# ADC.net
KiCad netlist of a schematic drawn in Altium Designer
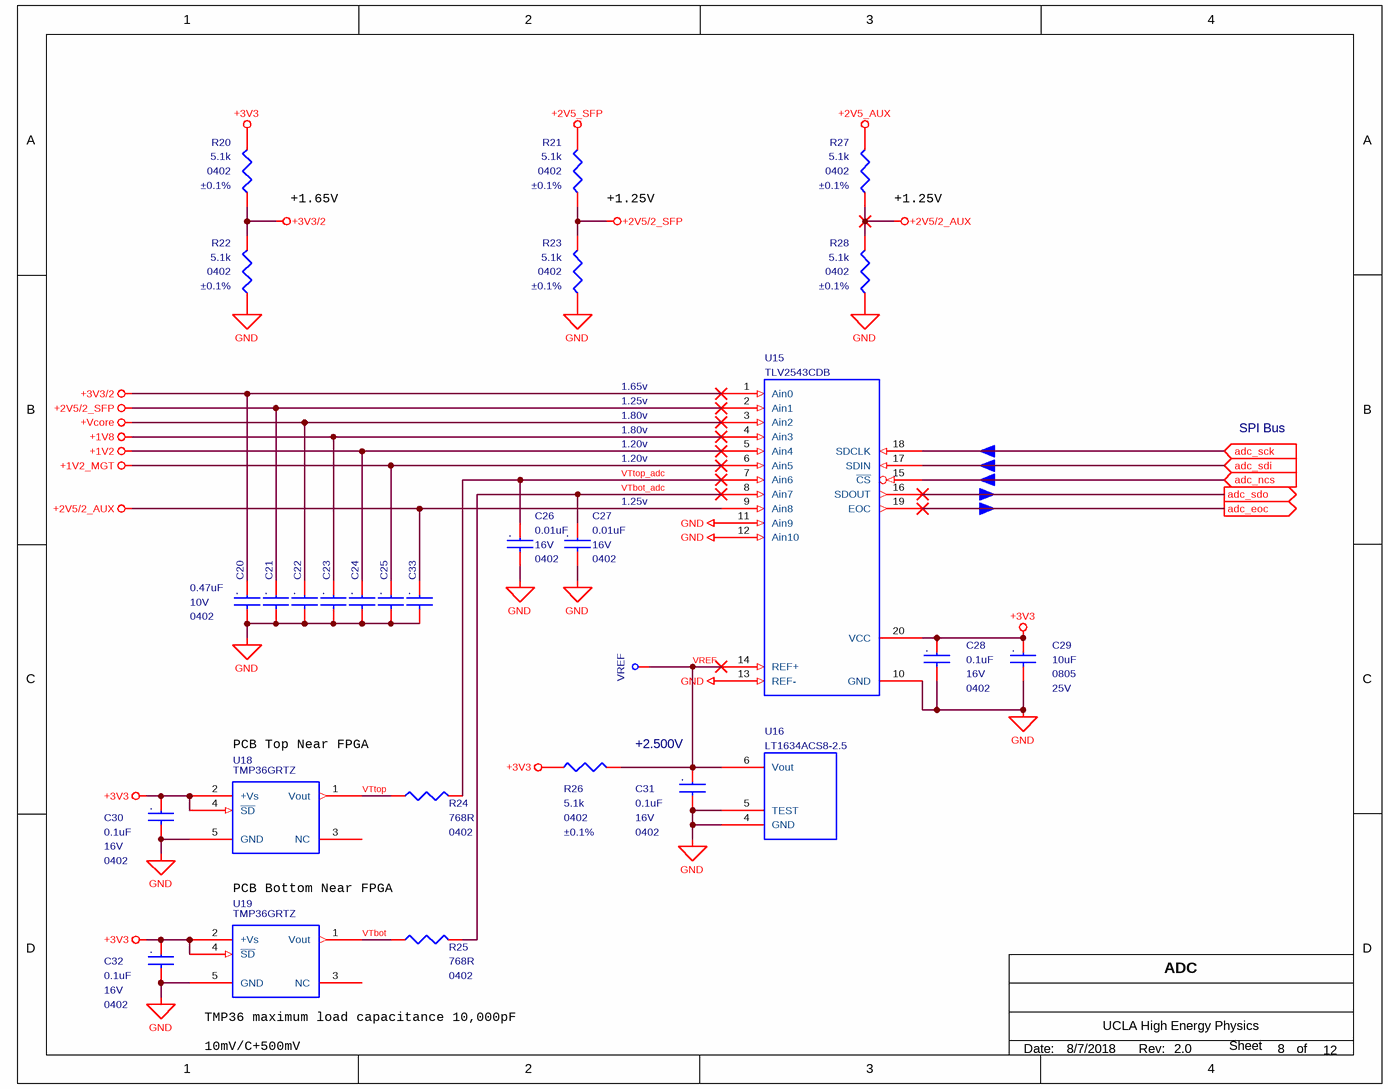
[diagram p0: ADC.SchDoc]

(export (version "E")
  (design (tool "Eeschema 10.0.6"))
  (components
    (comp (ref "C20")
      (value "0.47uF")
      (footprint "MC_S6/SM/C_0402_IPC")
      (description "CAP CER 0.47UF 10V X5R 0402")
      (fields
        (field (name "MANUFACTURER") "Murata Electronics North America")
        (field (name "MANUFACTURER PART NUMBER") "GRM155R61A474KE15J")
        (field (name "PACKAGE") "0402")
        (field (name "VOLTAGE - RATED") "10V")
      )
      (libsource (lib "ALCT_MEZ_SPARTAN6_Library") (part "GRM155R61A474KE15J"))
    )
    (comp (ref "C21")
      (value "0.47uF")
      (footprint "MC_S6/SM/C_0402_IPC")
      (description "CAP CER 0.47UF 10V X5R 0402")
      (fields
        (field (name "MANUFACTURER") "Murata Electronics North America")
        (field (name "MANUFACTURER PART NUMBER") "GRM155R61A474KE15J")
      )
      (libsource (lib "ALCT_MEZ_SPARTAN6_Library") (part "GRM155R61A474KE15J"))
    )
    (comp (ref "C22")
      (value "0.47uF")
      (footprint "MC_S6/SM/C_0402_IPC")
      (description "CAP CER 0.47UF 10V X5R 0402")
      (fields
        (field (name "MANUFACTURER") "Murata Electronics North America")
        (field (name "MANUFACTURER PART NUMBER") "GRM155R61A474KE15J")
      )
      (libsource (lib "ALCT_MEZ_SPARTAN6_Library") (part "GRM155R61A474KE15J"))
    )
    (comp (ref "C23")
      (value "0.47uF")
      (footprint "MC_S6/SM/C_0402_IPC")
      (description "CAP CER 0.47UF 10V X5R 0402")
      (fields
        (field (name "MANUFACTURER") "Murata Electronics North America")
        (field (name "MANUFACTURER PART NUMBER") "GRM155R61A474KE15J")
      )
      (libsource (lib "ALCT_MEZ_SPARTAN6_Library") (part "GRM155R61A474KE15J"))
    )
    (comp (ref "C24")
      (value "0.47uF")
      (footprint "MC_S6/SM/C_0402_IPC")
      (description "CAP CER 0.47UF 10V X5R 0402")
      (fields
        (field (name "MANUFACTURER") "Murata Electronics North America")
        (field (name "MANUFACTURER PART NUMBER") "GRM155R61A474KE15J")
      )
      (libsource (lib "ALCT_MEZ_SPARTAN6_Library") (part "GRM155R61A474KE15J"))
    )
    (comp (ref "C25")
      (value "0.47uF")
      (footprint "MC_S6/SM/C_0402_IPC")
      (description "CAP CER 0.47UF 10V X5R 0402")
      (fields
        (field (name "MANUFACTURER") "Murata Electronics North America")
        (field (name "MANUFACTURER PART NUMBER") "GRM155R61A474KE15J")
      )
      (libsource (lib "ALCT_MEZ_SPARTAN6_Library") (part "GRM155R61A474KE15J"))
    )
    (comp (ref "C26")
      (value "0.01uF")
      (footprint "MC_S6/SM/C_0402_IPC")
      (description "CAP CER 10nF 16V X7R 0402")
      (fields
        (field (name "MANUFACTURER") "KEMET")
        (field (name "MANUFACTURER PART NUMBER") "C0402C103K4RACTU")
        (field (name "VOLTAGE - RATED") "16V")
        (field (name "PACKAGE") "0402")
      )
      (libsource (lib "ALCT_MEZ_SPARTAN6_Library") (part "C0402C103K4RACTU"))
    )
    (comp (ref "C27")
      (value "0.01uF")
      (footprint "MC_S6/SM/C_0402_IPC")
      (description "CAP CER 10nF 16V X7R 0402")
      (fields
        (field (name "MANUFACTURER") "KEMET")
        (field (name "MANUFACTURER PART NUMBER") "C0402C103K4RACTU")
        (field (name "VOLTAGE - RATED") "16V")
        (field (name "PACKAGE") "0402")
      )
      (libsource (lib "ALCT_MEZ_SPARTAN6_Library") (part "C0402C103K4RACTU"))
    )
    (comp (ref "C28")
      (value "0.1uF")
      (footprint "MC_S6/SM/C_0402_IPC")
      (description "CAP CER 0.1UF 16V X7R 0402")
      (fields
        (field (name "MANUFACTURER") "KEMET")
        (field (name "MANUFACTURER PART NUMBER") "C0402C104K4RACTU")
        (field (name "PACKAGE") "0402")
        (field (name "VOLTAGE - RATED") "16V")
      )
      (libsource (lib "ALCT_MEZ_SPARTAN6_Library") (part "C0402C104K4RACTU"))
    )
    (comp (ref "C29")
      (value "10uF")
      (footprint "MC_S6/SM/C_0805_IPC")
      (description "CAP CER 10UF 25V X5R 0805")
      (fields
        (field (name "MANUFACTURER") "Murata Electronics North America")
        (field (name "MANUFACTURER PART NUMBER") "GRM21BR61E106KA73L")
        (field (name "VOLTAGE - RATED") "25V")
        (field (name "PACKAGE") "0805")
      )
      (libsource (lib "ALCT_MEZ_SPARTAN6_Library") (part "GRM21BR61E106KA73L"))
    )
    (comp (ref "C30")
      (value "0.1uF")
      (footprint "MC_S6/SM/C_0402_IPC")
      (description "CAP CER 0.1UF 16V X7R 0402")
      (fields
        (field (name "MANUFACTURER") "KEMET")
        (field (name "MANUFACTURER PART NUMBER") "C0402C104K4RACTU")
        (field (name "PACKAGE") "0402")
        (field (name "VOLTAGE - RATED") "16V")
      )
      (libsource (lib "ALCT_MEZ_SPARTAN6_Library") (part "C0402C104K4RACTU"))
    )
    (comp (ref "C31")
      (value "0.1uF")
      (footprint "MC_S6/SM/C_0402_IPC")
      (description "CAP CER 0.1UF 16V X7R 0402")
      (fields
        (field (name "MANUFACTURER") "KEMET")
        (field (name "MANUFACTURER PART NUMBER") "C0402C104K4RACTU")
        (field (name "PACKAGE") "0402")
        (field (name "VOLTAGE - RATED") "16V")
      )
      (libsource (lib "ALCT_MEZ_SPARTAN6_Library") (part "C0402C104K4RACTU"))
    )
    (comp (ref "C32")
      (value "0.1uF")
      (footprint "MC_S6/SM/C_0402_IPC")
      (description "CAP CER 0.1UF 16V X7R 0402")
      (fields
        (field (name "MANUFACTURER") "KEMET")
        (field (name "MANUFACTURER PART NUMBER") "C0402C104K4RACTU")
        (field (name "PACKAGE") "0402")
        (field (name "VOLTAGE - RATED") "16V")
      )
      (libsource (lib "ALCT_MEZ_SPARTAN6_Library") (part "C0402C104K4RACTU"))
    )
    (comp (ref "C33")
      (value "0.47uF")
      (footprint "MC_S6/SM/C_0402_IPC")
      (description "CAP CER 0.47UF 10V X5R 0402")
      (fields
        (field (name "MANUFACTURER") "Murata Electronics North America")
        (field (name "MANUFACTURER PART NUMBER") "GRM155R61A474KE15J")
      )
      (libsource (lib "ALCT_MEZ_SPARTAN6_Library") (part "GRM155R61A474KE15J"))
    )
    (comp (ref "R20")
      (value "5.1k")
      (footprint "MC_S6/SM/R_0402_IPC")
      (description "RES SMD 5.1K OHM 0.1% 1/16W 0402")
      (fields
        (field (name "TOLERANCE") "±0.1%")
        (field (name "MANUFACTURER") "Panasonic Electronic Components")
        (field (name "MANUFACTURER PART NUMBER") "ERA-2AEB512X")
        (field (name "SUPPLIER DEVICE PACKAGE") "0402")
      )
      (libsource (lib "ALCT_MEZ_SPARTAN6_Library") (part "ERA-2AEB512X"))
    )
    (comp (ref "R21")
      (value "5.1k")
      (footprint "MC_S6/SM/R_0402_IPC")
      (description "RES SMD 5.1K OHM 0.1% 1/16W 0402")
      (fields
        (field (name "TOLERANCE") "±0.1%")
        (field (name "MANUFACTURER") "Panasonic Electronic Components")
        (field (name "MANUFACTURER PART NUMBER") "ERA-2AEB512X")
        (field (name "SUPPLIER DEVICE PACKAGE") "0402")
      )
      (libsource (lib "ALCT_MEZ_SPARTAN6_Library") (part "ERA-2AEB512X"))
    )
    (comp (ref "R22")
      (value "5.1k")
      (footprint "MC_S6/SM/R_0402_IPC")
      (description "RES SMD 5.1K OHM 0.1% 1/16W 0402")
      (fields
        (field (name "TOLERANCE") "±0.1%")
        (field (name "MANUFACTURER") "Panasonic Electronic Components")
        (field (name "MANUFACTURER PART NUMBER") "ERA-2AEB512X")
        (field (name "SUPPLIER DEVICE PACKAGE") "0402")
      )
      (libsource (lib "ALCT_MEZ_SPARTAN6_Library") (part "ERA-2AEB512X"))
    )
    (comp (ref "R23")
      (value "5.1k")
      (footprint "MC_S6/SM/R_0402_IPC")
      (description "RES SMD 5.1K OHM 0.1% 1/16W 0402")
      (fields
        (field (name "TOLERANCE") "±0.1%")
        (field (name "MANUFACTURER") "Panasonic Electronic Components")
        (field (name "MANUFACTURER PART NUMBER") "ERA-2AEB512X")
        (field (name "SUPPLIER DEVICE PACKAGE") "0402")
      )
      (libsource (lib "ALCT_MEZ_SPARTAN6_Library") (part "ERA-2AEB512X"))
    )
    (comp (ref "R24")
      (value "768R")
      (footprint "MC_S6/SM/R_0402_IPC")
      (description "RES SMD 768 OHM 5.0% 1/10W 0402")
      (fields
        (field (name "MANUFACTURER") "Panasonic Electronic Components")
        (field (name "MANUFACTURER PART NUMBER") "ERJ-2RKF7680X")
        (field (name "SUPPLIER DEVICE PACKAGE") "0402")
      )
      (libsource (lib "ALCT_MEZ_SPARTAN6_Library") (part "ERJ-2RKF7680X"))
    )
    (comp (ref "R25")
      (value "768R")
      (footprint "MC_S6/SM/R_0402_IPC")
      (description "RES SMD 768 OHM 5.0% 1/10W 0402")
      (fields
        (field (name "TOLERANCE") "±1%")
        (field (name "MANUFACTURER") "Panasonic Electronic Components")
        (field (name "SUPPLIER DEVICE PACKAGE") "0402")
      )
      (libsource (lib "ALCT_MEZ_SPARTAN6_Library") (part "ERJ-2RKF7680X"))
    )
    (comp (ref "R26")
      (value "5.1k")
      (footprint "MC_S6/SM/R_0402_IPC")
      (description "RES SMD 5.1K OHM 0.1% 1/16W 0402")
      (fields
        (field (name "TOLERANCE") "±0.1%")
        (field (name "MANUFACTURER") "Panasonic Electronic Components")
        (field (name "MANUFACTURER PART NUMBER") "ERA-2AEB512X")
        (field (name "SUPPLIER DEVICE PACKAGE") "0402")
      )
      (libsource (lib "ALCT_MEZ_SPARTAN6_Library") (part "ERA-2AEB512X"))
    )
    (comp (ref "R27")
      (value "5.1k")
      (footprint "MC_S6/SM/R_0402_IPC")
      (description "RES SMD 5.1K OHM 0.1% 1/16W 0402")
      (fields
        (field (name "TOLERANCE") "±0.1%")
        (field (name "MANUFACTURER") "Panasonic Electronic Components")
        (field (name "MANUFACTURER PART NUMBER") "ERA-2AEB512X")
        (field (name "SUPPLIER DEVICE PACKAGE") "0402")
      )
      (libsource (lib "ALCT_MEZ_SPARTAN6_Library") (part "ERA-2AEB512X"))
    )
    (comp (ref "R28")
      (value "5.1k")
      (footprint "MC_S6/SM/R_0402_IPC")
      (description "RES SMD 5.1K OHM 0.1% 1/16W 0402")
      (fields
        (field (name "TOLERANCE") "±0.1%")
        (field (name "MANUFACTURER") "Panasonic Electronic Components")
        (field (name "MANUFACTURER PART NUMBER") "ERA-2AEB512X")
        (field (name "SUPPLIER DEVICE PACKAGE") "0402")
      )
      (libsource (lib "ALCT_MEZ_SPARTAN6_Library") (part "ERA-2AEB512X"))
    )
    (comp (ref "U15")
      (value "TLV2543CDB")
      (footprint "MC_S6/SM/ADC_DB20")
      (description "IC SERIAL OUT A/D 11-CH 20-SSOP")
      (fields
        (field (name "MANUFACTURER") "Texas Instruments")
        (field (name "MANUFACTURER PART NUMBER") "TLV2543CDBR")
      )
      (libsource (lib "ALCT_MEZ_SPARTAN6_Library") (part "TLV2543CDB"))
    )
    (comp (ref "U16")
      (value "LT1634ACS8-2.5")
      (footprint "MC_S6/SM/LT1634_SOIC8")
      (description "IC VREF SHUNT 2.5V 8SOIC")
      (fields
        (field (name "MANUFACTURER") "Linear Technology")
        (field (name "MANUFACTURER PART NUMBER") "LT1634ACS8-2.5#PBF")
      )
      (libsource (lib "ALCT_MEZ_SPARTAN6_Library") (part "LT1634_2.5V"))
    )
    (comp (ref "U18")
      (value "TMP36GRTZ")
      (footprint "MC_S6/SM/SOT23_RJ5")
      (description "SENSOR TEMP ANLG VOLT SOT-23-5")
      (fields
        (field (name "MANUFACTURER") "Analog Devices")
        (field (name "MANUFACTURER PART NUMBER") "TMP36GRTZ-REEL7")
      )
      (libsource (lib "ALCT_MEZ_SPARTAN6_Library") (part "TMP36GRTZ"))
    )
    (comp (ref "U19")
      (value "TMP36GRTZ")
      (footprint "MC_S6/SM/SOT23_RJ5")
      (description "SENSOR TEMP ANLG VOLT SOT-23-5")
      (fields
        (field (name "MANUFACTURER") "Analog Devices")
        (field (name "MANUFACTURER PART NUMBER") "TMP36GRTZ-REEL7")
      )
      (libsource (lib "ALCT_MEZ_SPARTAN6_Library") (part "TMP36GRTZ"))
    )
    (comp (ref "VREF")
      (value "Test Point Via")
      (footprint "MC_S6/TH/TPVIA")
      (libsource (lib "ALCT_MEZ_SPARTAN6_Library") (part "TPVIA"))
    )
  )
  (nets
    (net (code "1") (name "+1V2") (class "Default")
      (node (ref "C24") (pin "1") (pinfunction "1_1") (pintype "passive"))
      (node (ref "U15") (pin "5") (pinfunction "Ain4_5") (pintype "input"))
    )
    (net (code "2") (name "+1V2_MGT") (class "Default")
      (node (ref "C25") (pin "1") (pinfunction "1_1") (pintype "passive"))
      (node (ref "U15") (pin "6") (pinfunction "Ain5_6") (pintype "input"))
    )
    (net (code "3") (name "+1V8") (class "Default")
      (node (ref "C23") (pin "1") (pinfunction "1_1") (pintype "passive"))
      (node (ref "U15") (pin "4") (pinfunction "Ain3_4") (pintype "input"))
    )
    (net (code "4") (name "+2V5_AUX") (class "Default")
      (node (ref "R27") (pin "1") (pinfunction "1_1") (pintype "passive"))
    )
    (net (code "5") (name "+2V5_SFP") (class "Default")
      (node (ref "R21") (pin "1") (pinfunction "1_1") (pintype "passive"))
    )
    (net (code "6") (name "+2V5{slash}2_AUX") (class "Default")
      (node (ref "C33") (pin "1") (pinfunction "1_1") (pintype "passive"))
      (node (ref "R27") (pin "2") (pinfunction "2_2") (pintype "passive"))
      (node (ref "R28") (pin "1") (pinfunction "1_1") (pintype "passive"))
      (node (ref "U15") (pin "9") (pinfunction "Ain8_9") (pintype "input"))
    )
    (net (code "7") (name "+2V5{slash}2_SFP") (class "Default")
      (node (ref "C21") (pin "1") (pinfunction "1_1") (pintype "passive"))
      (node (ref "R21") (pin "2") (pinfunction "2_2") (pintype "passive"))
      (node (ref "R23") (pin "1") (pinfunction "1_1") (pintype "passive"))
      (node (ref "U15") (pin "2") (pinfunction "Ain1_2") (pintype "input"))
    )
    (net (code "8") (name "+3V3") (class "Default")
      (node (ref "C28") (pin "1") (pinfunction "1_1") (pintype "passive"))
      (node (ref "C29") (pin "1") (pinfunction "1_1") (pintype "passive"))
      (node (ref "C30") (pin "1") (pinfunction "1_1") (pintype "passive"))
      (node (ref "C32") (pin "1") (pinfunction "1_1") (pintype "passive"))
      (node (ref "R20") (pin "1") (pinfunction "1_1") (pintype "passive"))
      (node (ref "R26") (pin "1") (pinfunction "1_1") (pintype "passive"))
      (node (ref "U15") (pin "20") (pinfunction "VCC_20") (pintype "power_in"))
      (node (ref "U18") (pin "2") (pinfunction "+Vs_2") (pintype "power_in"))
      (node (ref "U18") (pin "4") (pinfunction "~{SD}_4") (pintype "input"))
      (node (ref "U19") (pin "2") (pinfunction "+Vs_2") (pintype "power_in"))
      (node (ref "U19") (pin "4") (pinfunction "~{SD}_4") (pintype "input"))
    )
    (net (code "9") (name "+3V3{slash}2") (class "Default")
      (node (ref "C20") (pin "1") (pinfunction "1_1") (pintype "passive"))
      (node (ref "R20") (pin "2") (pinfunction "2_2") (pintype "passive"))
      (node (ref "R22") (pin "1") (pinfunction "1_1") (pintype "passive"))
      (node (ref "U15") (pin "1") (pinfunction "Ain0_1") (pintype "input"))
    )
    (net (code "10") (name "+Vcore") (class "Default")
      (node (ref "C22") (pin "1") (pinfunction "1_1") (pintype "passive"))
      (node (ref "U15") (pin "3") (pinfunction "Ain2_3") (pintype "input"))
    )
    (net (code "11") (name "/VREF") (class "Default")
      (node (ref "C31") (pin "1") (pinfunction "1_1") (pintype "passive"))
      (node (ref "R26") (pin "2") (pinfunction "2_2") (pintype "passive"))
      (node (ref "U15") (pin "14") (pinfunction "REF+_14") (pintype "input"))
      (node (ref "U16") (pin "6") (pinfunction "Vout_6") (pintype "passive"))
      (node (ref "VREF") (pin "1") (pinfunction "In_1") (pintype "passive"))
    )
    (net (code "12") (name "/VTbot") (class "Default")
      (node (ref "R25") (pin "1") (pinfunction "1_1") (pintype "passive"))
      (node (ref "U19") (pin "1") (pinfunction "Vout_1") (pintype "output"))
    )
    (net (code "13") (name "/VTbot_adc") (class "Default")
      (node (ref "C27") (pin "1") (pinfunction "1_1") (pintype "passive"))
      (node (ref "R25") (pin "2") (pinfunction "2_2") (pintype "passive"))
      (node (ref "U15") (pin "8") (pinfunction "Ain7_8") (pintype "input"))
    )
    (net (code "14") (name "/VTtop") (class "Default")
      (node (ref "R24") (pin "1") (pinfunction "1_1") (pintype "passive"))
      (node (ref "U18") (pin "1") (pinfunction "Vout_1") (pintype "output"))
    )
    (net (code "15") (name "/VTtop_adc") (class "Default")
      (node (ref "C26") (pin "1") (pinfunction "1_1") (pintype "passive"))
      (node (ref "R24") (pin "2") (pinfunction "2_2") (pintype "passive"))
      (node (ref "U15") (pin "7") (pinfunction "Ain6_7") (pintype "input"))
    )
    (net (code "16") (name "/adc_eoc") (class "Default")
      (node (ref "U15") (pin "19") (pinfunction "EOC_19") (pintype "output+no_connect"))
    )
    (net (code "17") (name "/adc_ncs") (class "Default")
      (node (ref "U15") (pin "15") (pinfunction "~{CS}_15") (pintype "input"))
    )
    (net (code "18") (name "/adc_sck") (class "Default")
      (node (ref "U15") (pin "18") (pinfunction "SDCLK_18") (pintype "input"))
    )
    (net (code "19") (name "/adc_sdi") (class "Default")
      (node (ref "U15") (pin "17") (pinfunction "SDIN_17") (pintype "input"))
    )
    (net (code "20") (name "/adc_sdo") (class "Default")
      (node (ref "U15") (pin "16") (pinfunction "SDOUT_16") (pintype "output+no_connect"))
    )
    (net (code "21") (name "GND") (class "Default")
      (node (ref "C20") (pin "2") (pinfunction "2_2") (pintype "passive"))
      (node (ref "C21") (pin "2") (pinfunction "2_2") (pintype "passive"))
      (node (ref "C22") (pin "2") (pinfunction "2_2") (pintype "passive"))
      (node (ref "C23") (pin "2") (pinfunction "2_2") (pintype "passive"))
      (node (ref "C24") (pin "2") (pinfunction "2_2") (pintype "passive"))
      (node (ref "C25") (pin "2") (pinfunction "2_2") (pintype "passive"))
      (node (ref "C26") (pin "2") (pinfunction "2_2") (pintype "passive"))
      (node (ref "C27") (pin "2") (pinfunction "2_2") (pintype "passive"))
      (node (ref "C28") (pin "2") (pinfunction "2_2") (pintype "passive"))
      (node (ref "C29") (pin "2") (pinfunction "2_2") (pintype "passive"))
      (node (ref "C30") (pin "2") (pinfunction "2_2") (pintype "passive"))
      (node (ref "C31") (pin "2") (pinfunction "2_2") (pintype "passive"))
      (node (ref "C32") (pin "2") (pinfunction "2_2") (pintype "passive"))
      (node (ref "C33") (pin "2") (pinfunction "2_2") (pintype "passive"))
      (node (ref "R22") (pin "2") (pinfunction "2_2") (pintype "passive"))
      (node (ref "R23") (pin "2") (pinfunction "2_2") (pintype "passive"))
      (node (ref "R28") (pin "2") (pinfunction "2_2") (pintype "passive"))
      (node (ref "U15") (pin "10") (pinfunction "GND_10") (pintype "power_in"))
      (node (ref "U15") (pin "11") (pinfunction "Ain9_11") (pintype "input"))
      (node (ref "U15") (pin "12") (pinfunction "Ain10_12") (pintype "input"))
      (node (ref "U15") (pin "13") (pinfunction "REF-_13") (pintype "input"))
      (node (ref "U16") (pin "4") (pinfunction "GND_4") (pintype "power_in"))
      (node (ref "U16") (pin "5") (pinfunction "TEST_5") (pintype "passive"))
      (node (ref "U18") (pin "5") (pinfunction "GND_5") (pintype "power_in"))
      (node (ref "U19") (pin "5") (pinfunction "GND_5") (pintype "power_in"))
    )
    (net (code "22") (name "unconnected-(U18-NC-Pad3)") (class "Default")
      (node (ref "U18") (pin "3") (pinfunction "NC_3") (pintype "passive"))
    )
    (net (code "23") (name "unconnected-(U19-NC-Pad3)") (class "Default")
      (node (ref "U19") (pin "3") (pinfunction "NC_3") (pintype "passive"))
    )
  )
)
